# Sheet1.net
KiCad netlist of a schematic drawn in Altium Designer
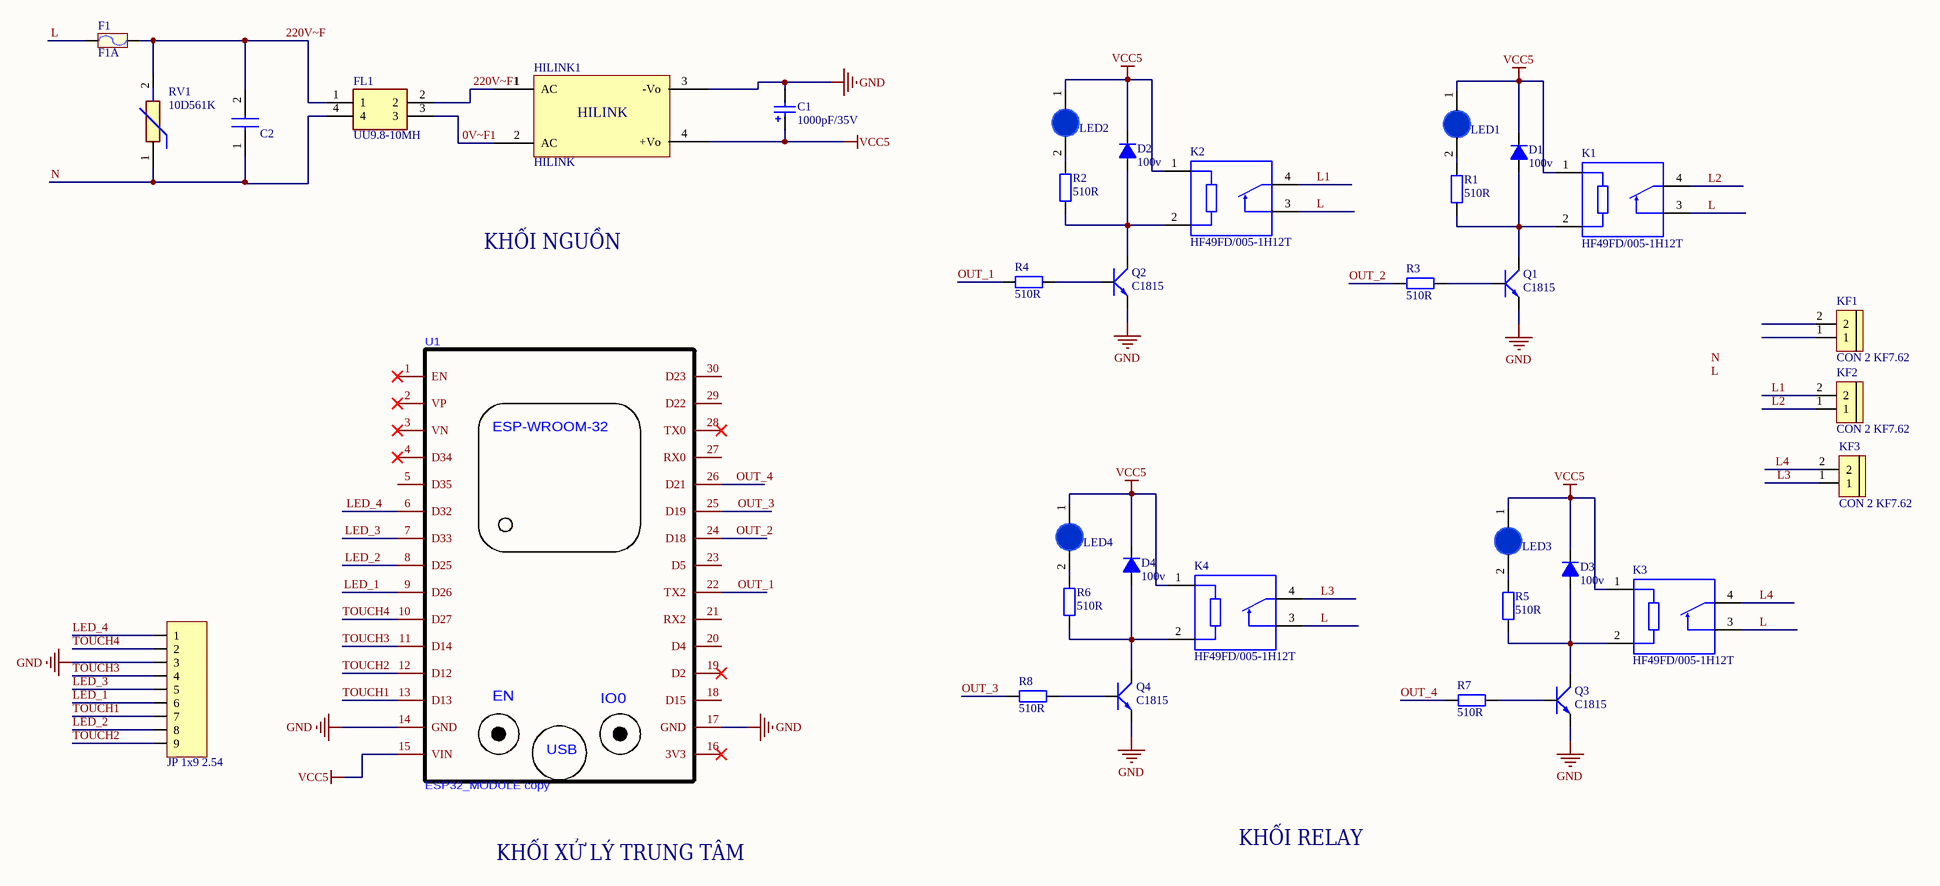
[diagram p0: Sheet1.SchDoc]

(export (version "E")
  (design (tool "Eeschema 10.0.6"))
  (components
    (comp (ref "C1")
      (value "1000pF/35V")
      (footprint "CP2/5")
      (description "Polarized Capacitor (Surface Mount)")
      (fields (field (name "Comment") "Cap Pol3") (field (name "PUBLISHER") "Altium Limited"))
      (libsource (lib "myLib_v1") (part "Cap Pol3"))
    )
    (comp (ref "C2")
      (value "R46KF3100JMP0K")
      (footprint "R46KF3100JMP0K")
      (description "Capacitor")
      (fields (field (name "MOUSER PART NUMBER") "80-R46KF3100JMP0K"))
      (libsource (lib "myLib_v1") (part "R46KF3100JMP0K"))
    )
    (comp (ref "D1")
      (value "100v")
      (footprint "DIODE 0.5A")
      (description "Cắm")
      (libsource (lib "Altium_Lib_by_KhueNguyenCreator") (part "Diode 1N4148"))
    )
    (comp (ref "D2")
      (value "100v")
      (footprint "DIODE 0.5A")
      (description "Cắm")
      (libsource (lib "Altium_Lib_by_KhueNguyenCreator") (part "Diode 1N4148"))
    )
    (comp (ref "D3")
      (value "100v")
      (footprint "DIODE 0.5A")
      (description "Cắm")
      (libsource (lib "Altium_Lib_by_KhueNguyenCreator") (part "Diode 1N4148"))
    )
    (comp (ref "D4")
      (value "100v")
      (footprint "DIODE 0.5A")
      (description "Cắm")
      (libsource (lib "Altium_Lib_by_KhueNguyenCreator") (part "Diode 1N4148"))
    )
    (comp (ref "F1")
      (value "F1A")
      (footprint "Fuse")
      (description "Fuse")
      (fields (field (name "DESIGNED BY") "VanDungEvn"))
      (libsource (lib "myLib_v1") (part "Fuse"))
    )
    (comp (ref "FL1")
      (value "UU9.8-10MH")
      (footprint "UU9810MH")
      (description "Filter")
      (libsource (lib "myLib_v1") (part "UU9.8-10MH"))
    )
    (comp (ref "HILINK1")
      (value "HILINK")
      (footprint "HILINK_1W")
      (libsource (lib "myLib_v1") (part "HILINK"))
    )
    (comp (ref "JP1")
      (value "JP 1x9 2.54")
      (footprint "JP 1x9 CT")
      (description "Cắm")
      (libsource (lib "Altium_Lib_by_KhueNguyenCreator") (part "JP 1x9 2.54 Cai Thang"))
    )
    (comp (ref "K1")
      (value "HF49FD/005-1H12T")
      (footprint "RELAY_HF49FD/005-1H12T")
      (description "Relay: electromagnetic; SPST-NO; Ucoil: 5VDC; 5A/250VAC; 5A/30VDC")
      (fields (field (name "MF") "Hongfa"))
      (libsource (lib "myLib_v1") (part "HF49FD/005-1H12T"))
    )
    (comp (ref "K2")
      (value "HF49FD/005-1H12T")
      (footprint "RELAY_HF49FD/005-1H12T")
      (description "Relay: electromagnetic; SPST-NO; Ucoil: 5VDC; 5A/250VAC; 5A/30VDC")
      (fields (field (name "MF") "Hongfa"))
      (libsource (lib "myLib_v1") (part "HF49FD/005-1H12T"))
    )
    (comp (ref "K3")
      (value "HF49FD/005-1H12T")
      (footprint "RELAY_HF49FD/005-1H12T")
      (description "Relay: electromagnetic; SPST-NO; Ucoil: 5VDC; 5A/250VAC; 5A/30VDC")
      (fields (field (name "MF") "Hongfa"))
      (libsource (lib "myLib_v1") (part "HF49FD/005-1H12T"))
    )
    (comp (ref "K4")
      (value "HF49FD/005-1H12T")
      (footprint "RELAY_HF49FD/005-1H12T")
      (description "Relay: electromagnetic; SPST-NO; Ucoil: 5VDC; 5A/250VAC; 5A/30VDC")
      (fields (field (name "MF") "Hongfa"))
      (libsource (lib "myLib_v1") (part "HF49FD/005-1H12T"))
    )
    (comp (ref "KF1")
      (value "CON 2 KF7.62")
      (footprint "CON 2 KF7.62")
      (description "Cắm")
      (libsource (lib "Altium_Lib_by_KhueNguyenCreator") (part "CON 2 KF7.62"))
    )
    (comp (ref "KF2")
      (value "CON 2 KF7.62")
      (footprint "CON 2 KF7.62")
      (description "Cắm")
      (libsource (lib "Altium_Lib_by_KhueNguyenCreator") (part "CON 2 KF7.62"))
    )
    (comp (ref "KF3")
      (value "CON 2 KF7.62")
      (footprint "CON 2 KF7.62")
      (description "Cắm")
      (libsource (lib "Altium_Lib_by_KhueNguyenCreator") (part "CON 2 KF7.62"))
    )
    (comp (ref "LED1")
      (value "LED 3mm")
      (footprint "LED-3MM-BLUE")
      (description "Cắm")
      (libsource (lib "myLib_v1") (part "LED 3mm Xanh Duong"))
    )
    (comp (ref "LED2")
      (value "LED 3mm")
      (footprint "LED-3MM-BLUE")
      (description "Cắm")
      (libsource (lib "myLib_v1") (part "LED 3mm Xanh Duong"))
    )
    (comp (ref "LED3")
      (value "LED 3mm")
      (footprint "LED-3MM-BLUE")
      (description "Cắm")
      (libsource (lib "myLib_v1") (part "LED 3mm Xanh Duong"))
    )
    (comp (ref "LED4")
      (value "LED 3mm")
      (footprint "LED-3MM-BLUE")
      (description "Cắm")
      (libsource (lib "myLib_v1") (part "LED 3mm Xanh Duong"))
    )
    (comp (ref "Q1")
      (value "C1815")
      (footprint "C1815_cam")
      (description "NPN 600mW, ECB")
      (libsource (lib "myLib_v1") (part "C1815"))
    )
    (comp (ref "Q2")
      (value "C1815")
      (footprint "C1815_cam")
      (description "NPN 600mW, ECB")
      (libsource (lib "myLib_v1") (part "C1815"))
    )
    (comp (ref "Q3")
      (value "C1815")
      (footprint "C1815_cam")
      (description "NPN 600mW, ECB")
      (libsource (lib "myLib_v1") (part "C1815"))
    )
    (comp (ref "Q4")
      (value "C1815")
      (footprint "C1815_cam")
      (description "NPN 600mW, ECB")
      (libsource (lib "myLib_v1") (part "C1815"))
    )
    (comp (ref "R1")
      (value "510R")
      (footprint "R1/4W")
      (description "Resistor 1/4W")
      (libsource (lib "myLib_v1") (part "R1/4W"))
    )
    (comp (ref "R2")
      (value "510R")
      (footprint "R1/4W")
      (description "Resistor 1/4W")
      (libsource (lib "myLib_v1") (part "R1/4W"))
    )
    (comp (ref "R3")
      (value "510R")
      (footprint "R1/4W")
      (description "Resistor 1/4W")
      (libsource (lib "myLib_v1") (part "R1/4W"))
    )
    (comp (ref "R4")
      (value "510R")
      (footprint "R1/4W")
      (description "Resistor 1/4W")
      (libsource (lib "myLib_v1") (part "R1/4W"))
    )
    (comp (ref "R5")
      (value "510R")
      (footprint "R1/4W")
      (description "Resistor 1/4W")
      (libsource (lib "myLib_v1") (part "R1/4W"))
    )
    (comp (ref "R6")
      (value "510R")
      (footprint "R1/4W")
      (description "Resistor 1/4W")
      (libsource (lib "myLib_v1") (part "R1/4W"))
    )
    (comp (ref "R7")
      (value "510R")
      (footprint "R1/4W")
      (description "Resistor 1/4W")
      (libsource (lib "myLib_v1") (part "R1/4W"))
    )
    (comp (ref "R8")
      (value "510R")
      (footprint "R1/4W")
      (description "Resistor 1/4W")
      (libsource (lib "myLib_v1") (part "R1/4W"))
    )
    (comp (ref "RV1")
      (value "10D561K")
      (footprint "10D561K")
      (description "Varistor")
      (fields
        (field (name "MANUFACTURER_PART_NUMBER") "MOV-10D561K")
        (field (name "MOUSER PART NUMBER") "652-MOV-10D561K")
      )
      (libsource (lib "myLib_v1") (part "10D561K"))
    )
    (comp (ref "U1")
      (value "ESP32_MODULE copy")
      (footprint "ESP32-WIFIMODULE-FOOTPRINT")
      (libsource (lib "myLib_v1") (part "ESP32_MODULE copy"))
    )
  )
  (nets
    (net (code "1") (name "/0V~F1") (class "Default")
      (node (ref "FL1") (pin "3") (pinfunction "3_3") (pintype "passive"))
      (node (ref "HILINK1") (pin "2") (pinfunction "AC_2") (pintype "passive"))
    )
    (net (code "2") (name "/220V~F") (class "Default")
      (node (ref "C2") (pin "2") (pinfunction "2_2") (pintype "passive"))
      (node (ref "F1") (pin "2") (pinfunction "2_2") (pintype "passive"))
      (node (ref "FL1") (pin "1") (pinfunction "1_1") (pintype "passive"))
      (node (ref "RV1") (pin "2") (pinfunction "2_2") (pintype "passive"))
    )
    (net (code "3") (name "/220V~F1") (class "Default")
      (node (ref "FL1") (pin "2") (pinfunction "2_2") (pintype "passive"))
      (node (ref "HILINK1") (pin "1") (pinfunction "AC_1") (pintype "passive"))
    )
    (net (code "4") (name "/L") (class "Default")
      (node (ref "F1") (pin "1") (pinfunction "1_1") (pintype "passive"))
      (node (ref "K1") (pin "3") (pinfunction "C2_3") (pintype "passive"))
      (node (ref "K2") (pin "3") (pinfunction "C2_3") (pintype "passive"))
      (node (ref "K3") (pin "3") (pinfunction "C2_3") (pintype "passive"))
      (node (ref "K4") (pin "3") (pinfunction "C2_3") (pintype "passive"))
    )
    (net (code "5") (name "/L1") (class "Default")
      (node (ref "K2") (pin "4") (pinfunction "C1_4") (pintype "passive"))
      (node (ref "KF2") (pin "2") (pinfunction "2_2") (pintype "passive"))
    )
    (net (code "6") (name "/L2") (class "Default")
      (node (ref "K1") (pin "4") (pinfunction "C1_4") (pintype "passive"))
      (node (ref "KF2") (pin "1") (pinfunction "1_1") (pintype "passive"))
    )
    (net (code "7") (name "/L3") (class "Default")
      (node (ref "K4") (pin "4") (pinfunction "C1_4") (pintype "passive"))
      (node (ref "KF3") (pin "1") (pinfunction "1_1") (pintype "passive"))
    )
    (net (code "8") (name "/L4") (class "Default")
      (node (ref "K3") (pin "4") (pinfunction "C1_4") (pintype "passive"))
      (node (ref "KF3") (pin "2") (pinfunction "2_2") (pintype "passive"))
    )
    (net (code "9") (name "/LED_1") (class "Default")
      (node (ref "JP1") (pin "6") (pinfunction "6_6") (pintype "passive"))
      (node (ref "U1") (pin "9") (pinfunction "D26_9") (pintype "passive"))
    )
    (net (code "10") (name "/LED_2") (class "Default")
      (node (ref "JP1") (pin "8") (pinfunction "8_8") (pintype "passive"))
      (node (ref "U1") (pin "8") (pinfunction "D25_8") (pintype "passive"))
    )
    (net (code "11") (name "/LED_3") (class "Default")
      (node (ref "JP1") (pin "5") (pinfunction "5_5") (pintype "passive"))
      (node (ref "U1") (pin "7") (pinfunction "D33_7") (pintype "passive"))
    )
    (net (code "12") (name "/LED_4") (class "Default")
      (node (ref "JP1") (pin "1") (pinfunction "1_1") (pintype "passive"))
      (node (ref "U1") (pin "6") (pinfunction "D32_6") (pintype "passive"))
    )
    (net (code "13") (name "/N") (class "Default")
      (node (ref "C2") (pin "1") (pinfunction "1_1") (pintype "passive"))
      (node (ref "FL1") (pin "4") (pinfunction "4_4") (pintype "passive"))
      (node (ref "RV1") (pin "1") (pinfunction "1_1") (pintype "passive"))
    )
    (net (code "14") (name "/OUT_1") (class "Default")
      (node (ref "R4") (pin "1") (pinfunction "1_1") (pintype "passive"))
      (node (ref "U1") (pin "22") (pinfunction "TX2_22") (pintype "passive"))
    )
    (net (code "15") (name "/OUT_2") (class "Default")
      (node (ref "R3") (pin "1") (pinfunction "1_1") (pintype "passive"))
      (node (ref "U1") (pin "24") (pinfunction "D18_24") (pintype "passive"))
    )
    (net (code "16") (name "/OUT_3") (class "Default")
      (node (ref "R8") (pin "1") (pinfunction "1_1") (pintype "passive"))
      (node (ref "U1") (pin "25") (pinfunction "D19_25") (pintype "passive"))
    )
    (net (code "17") (name "/OUT_4") (class "Default")
      (node (ref "R7") (pin "1") (pinfunction "1_1") (pintype "passive"))
      (node (ref "U1") (pin "26") (pinfunction "D21_26") (pintype "passive"))
    )
    (net (code "18") (name "/TOUCH1") (class "Default")
      (node (ref "JP1") (pin "7") (pinfunction "7_7") (pintype "passive"))
      (node (ref "U1") (pin "13") (pinfunction "D13_13") (pintype "passive"))
    )
    (net (code "19") (name "/TOUCH2") (class "Default")
      (node (ref "JP1") (pin "9") (pinfunction "9_9") (pintype "passive"))
      (node (ref "U1") (pin "12") (pinfunction "D12_12") (pintype "passive"))
    )
    (net (code "20") (name "/TOUCH3") (class "Default")
      (node (ref "JP1") (pin "4") (pinfunction "4_4") (pintype "passive"))
      (node (ref "U1") (pin "11") (pinfunction "D14_11") (pintype "passive"))
    )
    (net (code "21") (name "/TOUCH4") (class "Default")
      (node (ref "JP1") (pin "2") (pinfunction "2_2") (pintype "passive"))
      (node (ref "U1") (pin "10") (pinfunction "D27_10") (pintype "passive"))
    )
    (net (code "22") (name "GND") (class "Default")
      (node (ref "C1") (pin "2") (pinfunction "2_2") (pintype "passive"))
      (node (ref "HILINK1") (pin "3") (pinfunction "-Vo_3") (pintype "passive"))
      (node (ref "JP1") (pin "3") (pinfunction "3_3") (pintype "passive"))
      (node (ref "Q1") (pin "1") (pinfunction "E_1") (pintype "passive"))
      (node (ref "Q2") (pin "1") (pinfunction "E_1") (pintype "passive"))
      (node (ref "Q3") (pin "1") (pinfunction "E_1") (pintype "passive"))
      (node (ref "Q4") (pin "1") (pinfunction "E_1") (pintype "passive"))
      (node (ref "U1") (pin "14") (pinfunction "GND_14") (pintype "passive"))
      (node (ref "U1") (pin "17") (pinfunction "GND_17") (pintype "passive"))
    )
    (net (code "23") (name "Net-(D1-A)") (class "Default")
      (node (ref "D1") (pin "1") (pinfunction "A_1") (pintype "passive"))
      (node (ref "K1") (pin "2") (pinfunction "L2_2") (pintype "passive"))
      (node (ref "Q1") (pin "2") (pinfunction "C_2") (pintype "passive"))
      (node (ref "R1") (pin "2") (pinfunction "2_2") (pintype "passive"))
    )
    (net (code "24") (name "Net-(D2-A)") (class "Default")
      (node (ref "D2") (pin "1") (pinfunction "A_1") (pintype "passive"))
      (node (ref "K2") (pin "2") (pinfunction "L2_2") (pintype "passive"))
      (node (ref "Q2") (pin "2") (pinfunction "C_2") (pintype "passive"))
      (node (ref "R2") (pin "2") (pinfunction "2_2") (pintype "passive"))
    )
    (net (code "25") (name "Net-(D3-A)") (class "Default")
      (node (ref "D3") (pin "1") (pinfunction "A_1") (pintype "passive"))
      (node (ref "K3") (pin "2") (pinfunction "L2_2") (pintype "passive"))
      (node (ref "Q3") (pin "2") (pinfunction "C_2") (pintype "passive"))
      (node (ref "R5") (pin "2") (pinfunction "2_2") (pintype "passive"))
    )
    (net (code "26") (name "Net-(D4-A)") (class "Default")
      (node (ref "D4") (pin "1") (pinfunction "A_1") (pintype "passive"))
      (node (ref "K4") (pin "2") (pinfunction "L2_2") (pintype "passive"))
      (node (ref "Q4") (pin "2") (pinfunction "C_2") (pintype "passive"))
      (node (ref "R6") (pin "2") (pinfunction "2_2") (pintype "passive"))
    )
    (net (code "27") (name "Net-(LED1-K)") (class "Default")
      (node (ref "LED1") (pin "2") (pinfunction "K_2") (pintype "passive"))
      (node (ref "R1") (pin "1") (pinfunction "1_1") (pintype "passive"))
    )
    (net (code "28") (name "Net-(LED2-K)") (class "Default")
      (node (ref "LED2") (pin "2") (pinfunction "K_2") (pintype "passive"))
      (node (ref "R2") (pin "1") (pinfunction "1_1") (pintype "passive"))
    )
    (net (code "29") (name "Net-(LED3-K)") (class "Default")
      (node (ref "LED3") (pin "2") (pinfunction "K_2") (pintype "passive"))
      (node (ref "R5") (pin "1") (pinfunction "1_1") (pintype "passive"))
    )
    (net (code "30") (name "Net-(LED4-K)") (class "Default")
      (node (ref "LED4") (pin "2") (pinfunction "K_2") (pintype "passive"))
      (node (ref "R6") (pin "1") (pinfunction "1_1") (pintype "passive"))
    )
    (net (code "31") (name "Net-(Q1-B)") (class "Default")
      (node (ref "Q1") (pin "3") (pinfunction "B_3") (pintype "passive"))
      (node (ref "R3") (pin "2") (pinfunction "2_2") (pintype "passive"))
    )
    (net (code "32") (name "Net-(Q2-B)") (class "Default")
      (node (ref "Q2") (pin "3") (pinfunction "B_3") (pintype "passive"))
      (node (ref "R4") (pin "2") (pinfunction "2_2") (pintype "passive"))
    )
    (net (code "33") (name "Net-(Q3-B)") (class "Default")
      (node (ref "Q3") (pin "3") (pinfunction "B_3") (pintype "passive"))
      (node (ref "R7") (pin "2") (pinfunction "2_2") (pintype "passive"))
    )
    (net (code "34") (name "Net-(Q4-B)") (class "Default")
      (node (ref "Q4") (pin "3") (pinfunction "B_3") (pintype "passive"))
      (node (ref "R8") (pin "2") (pinfunction "2_2") (pintype "passive"))
    )
    (net (code "35") (name "VCC5") (class "Default")
      (node (ref "C1") (pin "1") (pinfunction "1_1") (pintype "passive"))
      (node (ref "D1") (pin "2") (pinfunction "K_2") (pintype "passive"))
      (node (ref "D2") (pin "2") (pinfunction "K_2") (pintype "passive"))
      (node (ref "D3") (pin "2") (pinfunction "K_2") (pintype "passive"))
      (node (ref "D4") (pin "2") (pinfunction "K_2") (pintype "passive"))
      (node (ref "HILINK1") (pin "4") (pinfunction "+Vo_4") (pintype "passive"))
      (node (ref "K1") (pin "1") (pinfunction "L1_1") (pintype "passive"))
      (node (ref "K2") (pin "1") (pinfunction "L1_1") (pintype "passive"))
      (node (ref "K3") (pin "1") (pinfunction "L1_1") (pintype "passive"))
      (node (ref "K4") (pin "1") (pinfunction "L1_1") (pintype "passive"))
      (node (ref "LED1") (pin "1") (pinfunction "A_1") (pintype "passive"))
      (node (ref "LED2") (pin "1") (pinfunction "A_1") (pintype "passive"))
      (node (ref "LED3") (pin "1") (pinfunction "A_1") (pintype "passive"))
      (node (ref "LED4") (pin "1") (pinfunction "A_1") (pintype "passive"))
      (node (ref "U1") (pin "15") (pinfunction "VIN_15") (pintype "passive"))
    )
    (net (code "36") (name "unconnected-(KF1-Pad1)") (class "Default")
      (node (ref "KF1") (pin "1") (pinfunction "1_1") (pintype "passive"))
    )
    (net (code "37") (name "unconnected-(KF1-Pad2)") (class "Default")
      (node (ref "KF1") (pin "2") (pinfunction "2_2") (pintype "passive"))
    )
    (net (code "38") (name "unconnected-(U1-3V3-Pad16)") (class "Default")
      (node (ref "U1") (pin "16") (pinfunction "3V3_16") (pintype "passive+no_connect"))
    )
    (net (code "39") (name "unconnected-(U1-D2-Pad19)") (class "Default")
      (node (ref "U1") (pin "19") (pinfunction "D2_19") (pintype "passive+no_connect"))
    )
    (net (code "40") (name "unconnected-(U1-D4-Pad20)") (class "Default")
      (node (ref "U1") (pin "20") (pinfunction "D4_20") (pintype "passive"))
    )
    (net (code "41") (name "unconnected-(U1-D5-Pad23)") (class "Default")
      (node (ref "U1") (pin "23") (pinfunction "D5_23") (pintype "passive"))
    )
    (net (code "42") (name "unconnected-(U1-D15-Pad18)") (class "Default")
      (node (ref "U1") (pin "18") (pinfunction "D15_18") (pintype "passive"))
    )
    (net (code "43") (name "unconnected-(U1-D22-Pad29)") (class "Default")
      (node (ref "U1") (pin "29") (pinfunction "D22_29") (pintype "passive"))
    )
    (net (code "44") (name "unconnected-(U1-D23-Pad30)") (class "Default")
      (node (ref "U1") (pin "30") (pinfunction "D23_30") (pintype "passive"))
    )
    (net (code "45") (name "unconnected-(U1-D34-Pad4)") (class "Default")
      (node (ref "U1") (pin "4") (pinfunction "D34_4") (pintype "passive+no_connect"))
    )
    (net (code "46") (name "unconnected-(U1-D35-Pad5)") (class "Default")
      (node (ref "U1") (pin "5") (pinfunction "D35_5") (pintype "passive"))
    )
    (net (code "47") (name "unconnected-(U1-EN-Pad1)") (class "Default")
      (node (ref "U1") (pin "1") (pinfunction "EN_1") (pintype "passive+no_connect"))
    )
    (net (code "48") (name "unconnected-(U1-RX0-Pad27)") (class "Default")
      (node (ref "U1") (pin "27") (pinfunction "RX0_27") (pintype "passive"))
    )
    (net (code "49") (name "unconnected-(U1-RX2-Pad21)") (class "Default")
      (node (ref "U1") (pin "21") (pinfunction "RX2_21") (pintype "passive"))
    )
    (net (code "50") (name "unconnected-(U1-TX0-Pad28)") (class "Default")
      (node (ref "U1") (pin "28") (pinfunction "TX0_28") (pintype "passive+no_connect"))
    )
    (net (code "51") (name "unconnected-(U1-VN-Pad3)") (class "Default")
      (node (ref "U1") (pin "3") (pinfunction "VN_3") (pintype "passive+no_connect"))
    )
    (net (code "52") (name "unconnected-(U1-VP-Pad2)") (class "Default")
      (node (ref "U1") (pin "2") (pinfunction "VP_2") (pintype "passive+no_connect"))
    )
  )
)
